# BMW_E34T_Rear_Lights.net
KiCad netlist of a schematic drawn in Altium Designer
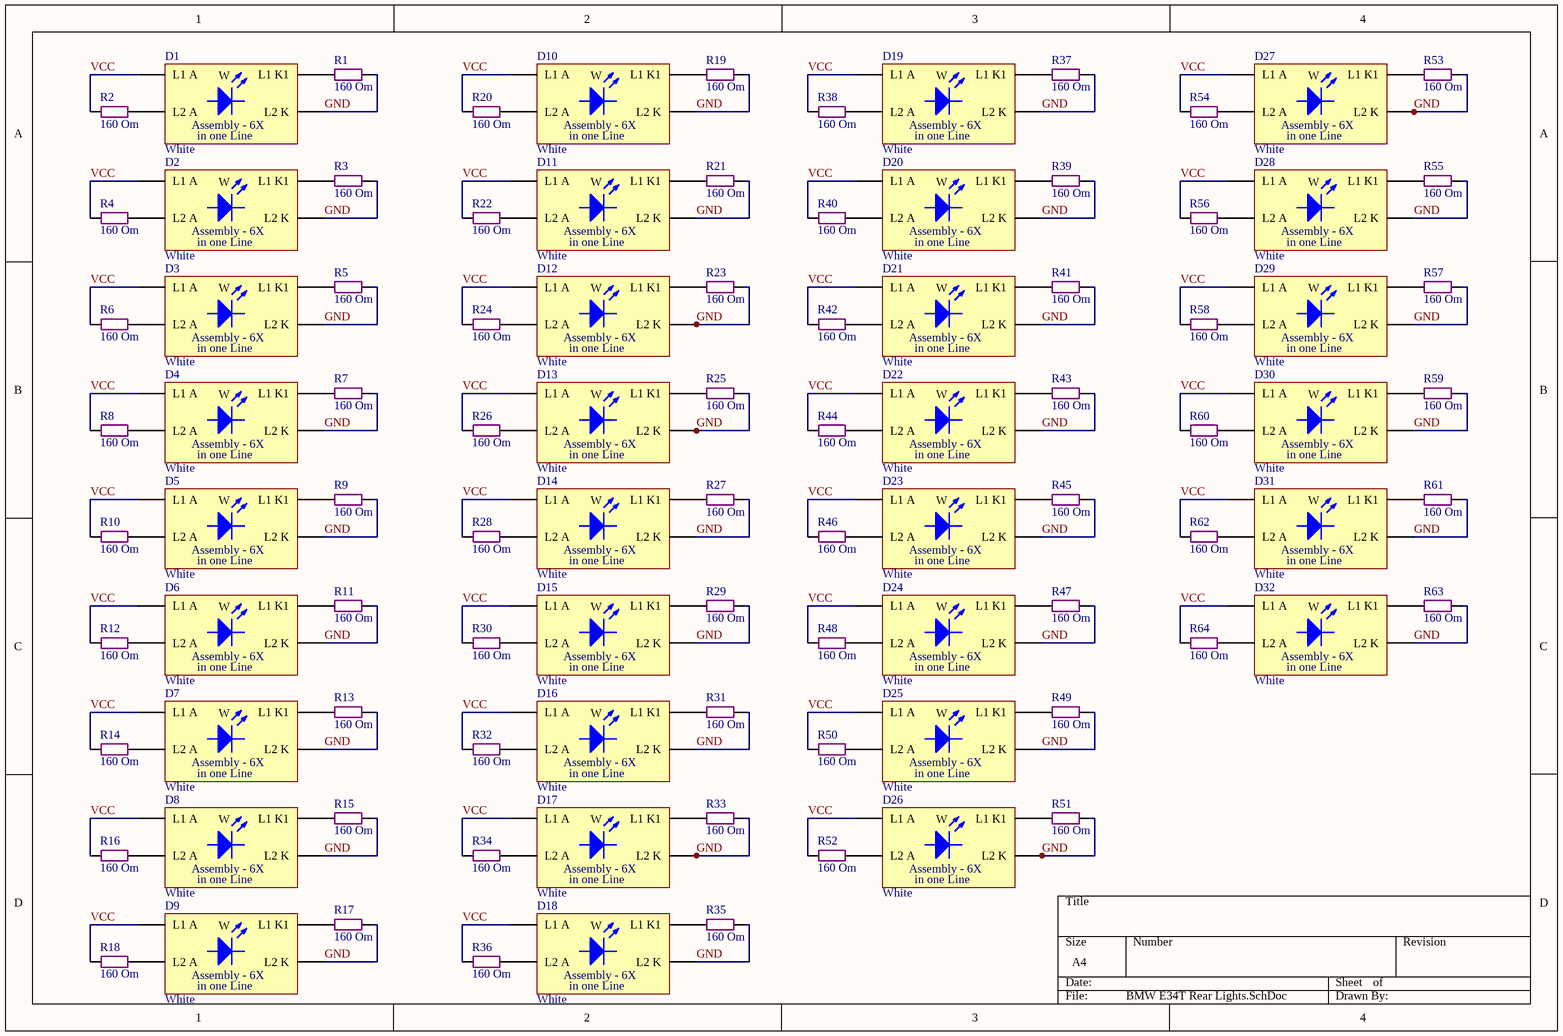
[diagram p0: BMW E34T Rear Lights.SchDoc]

(export (version "E")
  (design (tool "Eeschema 10.0.6"))
  (components
    (comp (ref "D1")
      (value "White")
      (footprint "LED:LED Assembly Round 5mm White 6X 0.5mm")
      (description "3.2-3.4v 25mA, 16-20cd")
      (libsource (lib "LED") (part "Led Assembly Round 5mm White 6X"))
    )
    (comp (ref "D2")
      (value "White")
      (footprint "LED:LED Assembly Round 5mm White 6X 0.5mm")
      (description "3.2-3.4v 25mA, 16-20cd")
      (libsource (lib "LED") (part "Led Assembly Round 5mm White 6X"))
    )
    (comp (ref "D3")
      (value "White")
      (footprint "LED:LED Assembly Round 5mm White 6X 0.5mm")
      (description "3.2-3.4v 25mA, 16-20cd")
      (libsource (lib "LED") (part "Led Assembly Round 5mm White 6X"))
    )
    (comp (ref "D4")
      (value "White")
      (footprint "LED:LED Assembly Round 5mm White 6X 0.5mm")
      (description "3.2-3.4v 25mA, 16-20cd")
      (libsource (lib "LED") (part "Led Assembly Round 5mm White 6X"))
    )
    (comp (ref "D5")
      (value "White")
      (footprint "LED:LED Assembly Round 5mm White 6X 0.5mm")
      (description "3.2-3.4v 25mA, 16-20cd")
      (libsource (lib "LED") (part "Led Assembly Round 5mm White 6X"))
    )
    (comp (ref "D6")
      (value "White")
      (footprint "LED:LED Assembly Round 5mm White 6X 0.5mm")
      (description "3.2-3.4v 25mA, 16-20cd")
      (libsource (lib "LED") (part "Led Assembly Round 5mm White 6X"))
    )
    (comp (ref "D7")
      (value "White")
      (footprint "LED:LED Assembly Round 5mm White 6X 0.5mm")
      (description "3.2-3.4v 25mA, 16-20cd")
      (libsource (lib "LED") (part "Led Assembly Round 5mm White 6X"))
    )
    (comp (ref "D8")
      (value "White")
      (footprint "LED:LED Assembly Round 5mm White 6X 0.5mm")
      (description "3.2-3.4v 25mA, 16-20cd")
      (libsource (lib "LED") (part "Led Assembly Round 5mm White 6X"))
    )
    (comp (ref "D9")
      (value "White")
      (footprint "LED:LED Assembly Round 5mm White 6X 0.5mm")
      (description "3.2-3.4v 25mA, 16-20cd")
      (libsource (lib "LED") (part "Led Assembly Round 5mm White 6X"))
    )
    (comp (ref "D10")
      (value "White")
      (footprint "LED:LED Assembly Round 5mm White 6X 0.5mm")
      (description "3.2-3.4v 25mA, 16-20cd")
      (libsource (lib "LED") (part "Led Assembly Round 5mm White 6X"))
    )
    (comp (ref "D11")
      (value "White")
      (footprint "LED:LED Assembly Round 5mm White 6X 0.5mm")
      (description "3.2-3.4v 25mA, 16-20cd")
      (libsource (lib "LED") (part "Led Assembly Round 5mm White 6X"))
    )
    (comp (ref "D12")
      (value "White")
      (footprint "LED:LED Assembly Round 5mm White 6X 0.5mm")
      (description "3.2-3.4v 25mA, 16-20cd")
      (libsource (lib "LED") (part "Led Assembly Round 5mm White 6X"))
    )
    (comp (ref "D13")
      (value "White")
      (footprint "LED:LED Assembly Round 5mm White 6X 0.5mm")
      (description "3.2-3.4v 25mA, 16-20cd")
      (libsource (lib "LED") (part "Led Assembly Round 5mm White 6X"))
    )
    (comp (ref "D14")
      (value "White")
      (footprint "LED:LED Assembly Round 5mm White 6X 0.5mm")
      (description "3.2-3.4v 25mA, 16-20cd")
      (libsource (lib "LED") (part "Led Assembly Round 5mm White 6X"))
    )
    (comp (ref "D15")
      (value "White")
      (footprint "LED:LED Assembly Round 5mm White 6X 0.5mm")
      (description "3.2-3.4v 25mA, 16-20cd")
      (libsource (lib "LED") (part "Led Assembly Round 5mm White 6X"))
    )
    (comp (ref "D16")
      (value "White")
      (footprint "LED:LED Assembly Round 5mm White 6X 0.5mm")
      (description "3.2-3.4v 25mA, 16-20cd")
      (libsource (lib "LED") (part "Led Assembly Round 5mm White 6X"))
    )
    (comp (ref "D17")
      (value "White")
      (footprint "LED:LED Assembly Round 5mm White 6X 0.5mm")
      (description "3.2-3.4v 25mA, 16-20cd")
      (libsource (lib "LED") (part "Led Assembly Round 5mm White 6X"))
    )
    (comp (ref "D18")
      (value "White")
      (footprint "LED:LED Assembly Round 5mm White 6X 0.5mm")
      (description "3.2-3.4v 25mA, 16-20cd")
      (libsource (lib "LED") (part "Led Assembly Round 5mm White 6X"))
    )
    (comp (ref "D19")
      (value "White")
      (footprint "LED:LED Assembly Round 5mm White 6X 0.5mm")
      (description "3.2-3.4v 25mA, 16-20cd")
      (libsource (lib "LED") (part "Led Assembly Round 5mm White 6X"))
    )
    (comp (ref "D20")
      (value "White")
      (footprint "LED:LED Assembly Round 5mm White 6X 0.5mm")
      (description "3.2-3.4v 25mA, 16-20cd")
      (libsource (lib "LED") (part "Led Assembly Round 5mm White 6X"))
    )
    (comp (ref "D21")
      (value "White")
      (footprint "LED:LED Assembly Round 5mm White 6X 0.5mm")
      (description "3.2-3.4v 25mA, 16-20cd")
      (libsource (lib "LED") (part "Led Assembly Round 5mm White 6X"))
    )
    (comp (ref "D22")
      (value "White")
      (footprint "LED:LED Assembly Round 5mm White 6X 0.5mm")
      (description "3.2-3.4v 25mA, 16-20cd")
      (libsource (lib "LED") (part "Led Assembly Round 5mm White 6X"))
    )
    (comp (ref "D23")
      (value "White")
      (footprint "LED:LED Assembly Round 5mm White 6X 0.5mm")
      (description "3.2-3.4v 25mA, 16-20cd")
      (libsource (lib "LED") (part "Led Assembly Round 5mm White 6X"))
    )
    (comp (ref "D24")
      (value "White")
      (footprint "LED:LED Assembly Round 5mm White 6X 0.5mm")
      (description "3.2-3.4v 25mA, 16-20cd")
      (libsource (lib "LED") (part "Led Assembly Round 5mm White 6X"))
    )
    (comp (ref "D25")
      (value "White")
      (footprint "LED:LED Assembly Round 5mm White 6X 0.5mm")
      (description "3.2-3.4v 25mA, 16-20cd")
      (libsource (lib "LED") (part "Led Assembly Round 5mm White 6X"))
    )
    (comp (ref "D26")
      (value "White")
      (footprint "LED:LED Assembly Round 5mm White 6X 0.5mm")
      (description "3.2-3.4v 25mA, 16-20cd")
      (libsource (lib "LED") (part "Led Assembly Round 5mm White 6X"))
    )
    (comp (ref "D27")
      (value "White")
      (footprint "LED:LED Assembly Round 5mm White 6X 0.5mm")
      (description "3.2-3.4v 25mA, 16-20cd")
      (libsource (lib "LED") (part "Led Assembly Round 5mm White 6X"))
    )
    (comp (ref "D28")
      (value "White")
      (footprint "LED:LED Assembly Round 5mm White 6X 0.5mm")
      (description "3.2-3.4v 25mA, 16-20cd")
      (libsource (lib "LED") (part "Led Assembly Round 5mm White 6X"))
    )
    (comp (ref "D29")
      (value "White")
      (footprint "LED:LED Assembly Round 5mm White 6X 0.5mm")
      (description "3.2-3.4v 25mA, 16-20cd")
      (libsource (lib "LED") (part "Led Assembly Round 5mm White 6X"))
    )
    (comp (ref "D30")
      (value "White")
      (footprint "LED:LED Assembly Round 5mm White 6X 0.5mm")
      (description "3.2-3.4v 25mA, 16-20cd")
      (libsource (lib "LED") (part "Led Assembly Round 5mm White 6X"))
    )
    (comp (ref "D31")
      (value "White")
      (footprint "LED:LED Assembly Round 5mm White 6X 0.5mm")
      (description "3.2-3.4v 25mA, 16-20cd")
      (libsource (lib "LED") (part "Led Assembly Round 5mm White 6X"))
    )
    (comp (ref "D32")
      (value "White")
      (footprint "LED:LED Assembly Round 5mm White 6X 0.5mm")
      (description "3.2-3.4v 25mA, 16-20cd")
      (libsource (lib "LED") (part "Led Assembly Round 5mm White 6X"))
    )
    (comp (ref "R1")
      (value "160 Om")
      (footprint "SMD 0805 (2012)")
      (libsource (lib "PassiveComponents") (part "Res SMD 0805"))
    )
    (comp (ref "R2")
      (value "160 Om")
      (footprint "SMD 0805 (2012)")
      (libsource (lib "PassiveComponents") (part "Res SMD 0805"))
    )
    (comp (ref "R3")
      (value "160 Om")
      (footprint "SMD 0805 (2012)")
      (libsource (lib "PassiveComponents") (part "Res SMD 0805"))
    )
    (comp (ref "R4")
      (value "160 Om")
      (footprint "SMD 0805 (2012)")
      (libsource (lib "PassiveComponents") (part "Res SMD 0805"))
    )
    (comp (ref "R5")
      (value "160 Om")
      (footprint "SMD 0805 (2012)")
      (libsource (lib "PassiveComponents") (part "Res SMD 0805"))
    )
    (comp (ref "R6")
      (value "160 Om")
      (footprint "SMD 0805 (2012)")
      (libsource (lib "PassiveComponents") (part "Res SMD 0805"))
    )
    (comp (ref "R7")
      (value "160 Om")
      (footprint "SMD 0805 (2012)")
      (libsource (lib "PassiveComponents") (part "Res SMD 0805"))
    )
    (comp (ref "R8")
      (value "160 Om")
      (footprint "SMD 0805 (2012)")
      (libsource (lib "PassiveComponents") (part "Res SMD 0805"))
    )
    (comp (ref "R9")
      (value "160 Om")
      (footprint "SMD 0805 (2012)")
      (libsource (lib "PassiveComponents") (part "Res SMD 0805"))
    )
    (comp (ref "R10")
      (value "160 Om")
      (footprint "SMD 0805 (2012)")
      (libsource (lib "PassiveComponents") (part "Res SMD 0805"))
    )
    (comp (ref "R11")
      (value "160 Om")
      (footprint "SMD 0805 (2012)")
      (libsource (lib "PassiveComponents") (part "Res SMD 0805"))
    )
    (comp (ref "R12")
      (value "160 Om")
      (footprint "SMD 0805 (2012)")
      (libsource (lib "PassiveComponents") (part "Res SMD 0805"))
    )
    (comp (ref "R13")
      (value "160 Om")
      (footprint "SMD 0805 (2012)")
      (libsource (lib "PassiveComponents") (part "Res SMD 0805"))
    )
    (comp (ref "R14")
      (value "160 Om")
      (footprint "SMD 0805 (2012)")
      (libsource (lib "PassiveComponents") (part "Res SMD 0805"))
    )
    (comp (ref "R15")
      (value "160 Om")
      (footprint "SMD 0805 (2012)")
      (libsource (lib "PassiveComponents") (part "Res SMD 0805"))
    )
    (comp (ref "R16")
      (value "160 Om")
      (footprint "SMD 0805 (2012)")
      (libsource (lib "PassiveComponents") (part "Res SMD 0805"))
    )
    (comp (ref "R17")
      (value "160 Om")
      (footprint "SMD 0805 (2012)")
      (libsource (lib "PassiveComponents") (part "Res SMD 0805"))
    )
    (comp (ref "R18")
      (value "160 Om")
      (footprint "SMD 0805 (2012)")
      (libsource (lib "PassiveComponents") (part "Res SMD 0805"))
    )
    (comp (ref "R19")
      (value "160 Om")
      (footprint "SMD 0805 (2012)")
      (libsource (lib "PassiveComponents") (part "Res SMD 0805"))
    )
    (comp (ref "R20")
      (value "160 Om")
      (footprint "SMD 0805 (2012)")
      (libsource (lib "PassiveComponents") (part "Res SMD 0805"))
    )
    (comp (ref "R21")
      (value "160 Om")
      (footprint "SMD 0805 (2012)")
      (libsource (lib "PassiveComponents") (part "Res SMD 0805"))
    )
    (comp (ref "R22")
      (value "160 Om")
      (footprint "SMD 0805 (2012)")
      (libsource (lib "PassiveComponents") (part "Res SMD 0805"))
    )
    (comp (ref "R23")
      (value "160 Om")
      (footprint "SMD 0805 (2012)")
      (libsource (lib "PassiveComponents") (part "Res SMD 0805"))
    )
    (comp (ref "R24")
      (value "160 Om")
      (footprint "SMD 0805 (2012)")
      (libsource (lib "PassiveComponents") (part "Res SMD 0805"))
    )
    (comp (ref "R25")
      (value "160 Om")
      (footprint "SMD 0805 (2012)")
      (libsource (lib "PassiveComponents") (part "Res SMD 0805"))
    )
    (comp (ref "R26")
      (value "160 Om")
      (footprint "SMD 0805 (2012)")
      (libsource (lib "PassiveComponents") (part "Res SMD 0805"))
    )
    (comp (ref "R27")
      (value "160 Om")
      (footprint "SMD 0805 (2012)")
      (libsource (lib "PassiveComponents") (part "Res SMD 0805"))
    )
    (comp (ref "R28")
      (value "160 Om")
      (footprint "SMD 0805 (2012)")
      (libsource (lib "PassiveComponents") (part "Res SMD 0805"))
    )
    (comp (ref "R29")
      (value "160 Om")
      (footprint "SMD 0805 (2012)")
      (libsource (lib "PassiveComponents") (part "Res SMD 0805"))
    )
    (comp (ref "R30")
      (value "160 Om")
      (footprint "SMD 0805 (2012)")
      (libsource (lib "PassiveComponents") (part "Res SMD 0805"))
    )
    (comp (ref "R31")
      (value "160 Om")
      (footprint "SMD 0805 (2012)")
      (libsource (lib "PassiveComponents") (part "Res SMD 0805"))
    )
    (comp (ref "R32")
      (value "160 Om")
      (footprint "SMD 0805 (2012)")
      (libsource (lib "PassiveComponents") (part "Res SMD 0805"))
    )
    (comp (ref "R33")
      (value "160 Om")
      (footprint "SMD 0805 (2012)")
      (libsource (lib "PassiveComponents") (part "Res SMD 0805"))
    )
    (comp (ref "R34")
      (value "160 Om")
      (footprint "SMD 0805 (2012)")
      (libsource (lib "PassiveComponents") (part "Res SMD 0805"))
    )
    (comp (ref "R35")
      (value "160 Om")
      (footprint "SMD 0805 (2012)")
      (libsource (lib "PassiveComponents") (part "Res SMD 0805"))
    )
    (comp (ref "R36")
      (value "160 Om")
      (footprint "SMD 0805 (2012)")
      (libsource (lib "PassiveComponents") (part "Res SMD 0805"))
    )
    (comp (ref "R37")
      (value "160 Om")
      (footprint "SMD 0805 (2012)")
      (libsource (lib "PassiveComponents") (part "Res SMD 0805"))
    )
    (comp (ref "R38")
      (value "160 Om")
      (footprint "SMD 0805 (2012)")
      (libsource (lib "PassiveComponents") (part "Res SMD 0805"))
    )
    (comp (ref "R39")
      (value "160 Om")
      (footprint "SMD 0805 (2012)")
      (libsource (lib "PassiveComponents") (part "Res SMD 0805"))
    )
    (comp (ref "R40")
      (value "160 Om")
      (footprint "SMD 0805 (2012)")
      (libsource (lib "PassiveComponents") (part "Res SMD 0805"))
    )
    (comp (ref "R41")
      (value "160 Om")
      (footprint "SMD 0805 (2012)")
      (libsource (lib "PassiveComponents") (part "Res SMD 0805"))
    )
    (comp (ref "R42")
      (value "160 Om")
      (footprint "SMD 0805 (2012)")
      (libsource (lib "PassiveComponents") (part "Res SMD 0805"))
    )
    (comp (ref "R43")
      (value "160 Om")
      (footprint "SMD 0805 (2012)")
      (libsource (lib "PassiveComponents") (part "Res SMD 0805"))
    )
    (comp (ref "R44")
      (value "160 Om")
      (footprint "SMD 0805 (2012)")
      (libsource (lib "PassiveComponents") (part "Res SMD 0805"))
    )
    (comp (ref "R45")
      (value "160 Om")
      (footprint "SMD 0805 (2012)")
      (libsource (lib "PassiveComponents") (part "Res SMD 0805"))
    )
    (comp (ref "R46")
      (value "160 Om")
      (footprint "SMD 0805 (2012)")
      (libsource (lib "PassiveComponents") (part "Res SMD 0805"))
    )
    (comp (ref "R47")
      (value "160 Om")
      (footprint "SMD 0805 (2012)")
      (libsource (lib "PassiveComponents") (part "Res SMD 0805"))
    )
    (comp (ref "R48")
      (value "160 Om")
      (footprint "SMD 0805 (2012)")
      (libsource (lib "PassiveComponents") (part "Res SMD 0805"))
    )
    (comp (ref "R49")
      (value "160 Om")
      (footprint "SMD 0805 (2012)")
      (libsource (lib "PassiveComponents") (part "Res SMD 0805"))
    )
    (comp (ref "R50")
      (value "160 Om")
      (footprint "SMD 0805 (2012)")
      (libsource (lib "PassiveComponents") (part "Res SMD 0805"))
    )
    (comp (ref "R51")
      (value "160 Om")
      (footprint "SMD 0805 (2012)")
      (libsource (lib "PassiveComponents") (part "Res SMD 0805"))
    )
    (comp (ref "R52")
      (value "160 Om")
      (footprint "SMD 0805 (2012)")
      (libsource (lib "PassiveComponents") (part "Res SMD 0805"))
    )
    (comp (ref "R53")
      (value "160 Om")
      (footprint "SMD 0805 (2012)")
      (libsource (lib "PassiveComponents") (part "Res SMD 0805"))
    )
    (comp (ref "R54")
      (value "160 Om")
      (footprint "SMD 0805 (2012)")
      (libsource (lib "PassiveComponents") (part "Res SMD 0805"))
    )
    (comp (ref "R55")
      (value "160 Om")
      (footprint "SMD 0805 (2012)")
      (libsource (lib "PassiveComponents") (part "Res SMD 0805"))
    )
    (comp (ref "R56")
      (value "160 Om")
      (footprint "SMD 0805 (2012)")
      (libsource (lib "PassiveComponents") (part "Res SMD 0805"))
    )
    (comp (ref "R57")
      (value "160 Om")
      (footprint "SMD 0805 (2012)")
      (libsource (lib "PassiveComponents") (part "Res SMD 0805"))
    )
    (comp (ref "R58")
      (value "160 Om")
      (footprint "SMD 0805 (2012)")
      (libsource (lib "PassiveComponents") (part "Res SMD 0805"))
    )
    (comp (ref "R59")
      (value "160 Om")
      (footprint "SMD 0805 (2012)")
      (libsource (lib "PassiveComponents") (part "Res SMD 0805"))
    )
    (comp (ref "R60")
      (value "160 Om")
      (footprint "SMD 0805 (2012)")
      (libsource (lib "PassiveComponents") (part "Res SMD 0805"))
    )
    (comp (ref "R61")
      (value "160 Om")
      (footprint "SMD 0805 (2012)")
      (libsource (lib "PassiveComponents") (part "Res SMD 0805"))
    )
    (comp (ref "R62")
      (value "160 Om")
      (footprint "SMD 0805 (2012)")
      (libsource (lib "PassiveComponents") (part "Res SMD 0805"))
    )
    (comp (ref "R63")
      (value "160 Om")
      (footprint "SMD 0805 (2012)")
      (libsource (lib "PassiveComponents") (part "Res SMD 0805"))
    )
    (comp (ref "R64")
      (value "160 Om")
      (footprint "SMD 0805 (2012)")
      (libsource (lib "PassiveComponents") (part "Res SMD 0805"))
    )
  )
  (nets
    (net (code "1") (name "/GND") (class "Default")
      (node (ref "D1") (pin "K2") (pinfunction "L2_K_K2") (pintype "passive"))
      (node (ref "D10") (pin "K2") (pinfunction "L2_K_K2") (pintype "passive"))
      (node (ref "D11") (pin "K2") (pinfunction "L2_K_K2") (pintype "passive"))
      (node (ref "D12") (pin "K2") (pinfunction "L2_K_K2") (pintype "passive"))
      (node (ref "D13") (pin "K2") (pinfunction "L2_K_K2") (pintype "passive"))
      (node (ref "D14") (pin "K2") (pinfunction "L2_K_K2") (pintype "passive"))
      (node (ref "D15") (pin "K2") (pinfunction "L2_K_K2") (pintype "passive"))
      (node (ref "D16") (pin "K2") (pinfunction "L2_K_K2") (pintype "passive"))
      (node (ref "D17") (pin "K2") (pinfunction "L2_K_K2") (pintype "passive"))
      (node (ref "D18") (pin "K2") (pinfunction "L2_K_K2") (pintype "passive"))
      (node (ref "D19") (pin "K2") (pinfunction "L2_K_K2") (pintype "passive"))
      (node (ref "D2") (pin "K2") (pinfunction "L2_K_K2") (pintype "passive"))
      (node (ref "D20") (pin "K2") (pinfunction "L2_K_K2") (pintype "passive"))
      (node (ref "D21") (pin "K2") (pinfunction "L2_K_K2") (pintype "passive"))
      (node (ref "D22") (pin "K2") (pinfunction "L2_K_K2") (pintype "passive"))
      (node (ref "D23") (pin "K2") (pinfunction "L2_K_K2") (pintype "passive"))
      (node (ref "D24") (pin "K2") (pinfunction "L2_K_K2") (pintype "passive"))
      (node (ref "D25") (pin "K2") (pinfunction "L2_K_K2") (pintype "passive"))
      (node (ref "D26") (pin "K2") (pinfunction "L2_K_K2") (pintype "passive"))
      (node (ref "D27") (pin "K2") (pinfunction "L2_K_K2") (pintype "passive"))
      (node (ref "D28") (pin "K2") (pinfunction "L2_K_K2") (pintype "passive"))
      (node (ref "D29") (pin "K2") (pinfunction "L2_K_K2") (pintype "passive"))
      (node (ref "D3") (pin "K2") (pinfunction "L2_K_K2") (pintype "passive"))
      (node (ref "D30") (pin "K2") (pinfunction "L2_K_K2") (pintype "passive"))
      (node (ref "D31") (pin "K2") (pinfunction "L2_K_K2") (pintype "passive"))
      (node (ref "D32") (pin "K2") (pinfunction "L2_K_K2") (pintype "passive"))
      (node (ref "D4") (pin "K2") (pinfunction "L2_K_K2") (pintype "passive"))
      (node (ref "D5") (pin "K2") (pinfunction "L2_K_K2") (pintype "passive"))
      (node (ref "D6") (pin "K2") (pinfunction "L2_K_K2") (pintype "passive"))
      (node (ref "D7") (pin "K2") (pinfunction "L2_K_K2") (pintype "passive"))
      (node (ref "D8") (pin "K2") (pinfunction "L2_K_K2") (pintype "passive"))
      (node (ref "D9") (pin "K2") (pinfunction "L2_K_K2") (pintype "passive"))
      (node (ref "R1") (pin "2") (pinfunction "2_2") (pintype "passive"))
      (node (ref "R11") (pin "2") (pinfunction "2_2") (pintype "passive"))
      (node (ref "R13") (pin "2") (pinfunction "2_2") (pintype "passive"))
      (node (ref "R15") (pin "2") (pinfunction "2_2") (pintype "passive"))
      (node (ref "R17") (pin "2") (pinfunction "2_2") (pintype "passive"))
      (node (ref "R19") (pin "2") (pinfunction "2_2") (pintype "passive"))
      (node (ref "R21") (pin "2") (pinfunction "2_2") (pintype "passive"))
      (node (ref "R23") (pin "2") (pinfunction "2_2") (pintype "passive"))
      (node (ref "R25") (pin "2") (pinfunction "2_2") (pintype "passive"))
      (node (ref "R27") (pin "2") (pinfunction "2_2") (pintype "passive"))
      (node (ref "R29") (pin "2") (pinfunction "2_2") (pintype "passive"))
      (node (ref "R3") (pin "2") (pinfunction "2_2") (pintype "passive"))
      (node (ref "R31") (pin "2") (pinfunction "2_2") (pintype "passive"))
      (node (ref "R33") (pin "2") (pinfunction "2_2") (pintype "passive"))
      (node (ref "R35") (pin "2") (pinfunction "2_2") (pintype "passive"))
      (node (ref "R37") (pin "2") (pinfunction "2_2") (pintype "passive"))
      (node (ref "R39") (pin "2") (pinfunction "2_2") (pintype "passive"))
      (node (ref "R41") (pin "2") (pinfunction "2_2") (pintype "passive"))
      (node (ref "R43") (pin "2") (pinfunction "2_2") (pintype "passive"))
      (node (ref "R45") (pin "2") (pinfunction "2_2") (pintype "passive"))
      (node (ref "R47") (pin "2") (pinfunction "2_2") (pintype "passive"))
      (node (ref "R49") (pin "2") (pinfunction "2_2") (pintype "passive"))
      (node (ref "R5") (pin "2") (pinfunction "2_2") (pintype "passive"))
      (node (ref "R51") (pin "2") (pinfunction "2_2") (pintype "passive"))
      (node (ref "R53") (pin "2") (pinfunction "2_2") (pintype "passive"))
      (node (ref "R55") (pin "2") (pinfunction "2_2") (pintype "passive"))
      (node (ref "R57") (pin "2") (pinfunction "2_2") (pintype "passive"))
      (node (ref "R59") (pin "2") (pinfunction "2_2") (pintype "passive"))
      (node (ref "R61") (pin "2") (pinfunction "2_2") (pintype "passive"))
      (node (ref "R63") (pin "2") (pinfunction "2_2") (pintype "passive"))
      (node (ref "R7") (pin "2") (pinfunction "2_2") (pintype "passive"))
      (node (ref "R9") (pin "2") (pinfunction "2_2") (pintype "passive"))
    )
    (net (code "2") (name "/VCC") (class "Default")
      (node (ref "D1") (pin "A1") (pinfunction "L1_A_A1") (pintype "passive"))
      (node (ref "D10") (pin "A1") (pinfunction "L1_A_A1") (pintype "passive"))
      (node (ref "D11") (pin "A1") (pinfunction "L1_A_A1") (pintype "passive"))
      (node (ref "D12") (pin "A1") (pinfunction "L1_A_A1") (pintype "passive"))
      (node (ref "D13") (pin "A1") (pinfunction "L1_A_A1") (pintype "passive"))
      (node (ref "D14") (pin "A1") (pinfunction "L1_A_A1") (pintype "passive"))
      (node (ref "D15") (pin "A1") (pinfunction "L1_A_A1") (pintype "passive"))
      (node (ref "D16") (pin "A1") (pinfunction "L1_A_A1") (pintype "passive"))
      (node (ref "D17") (pin "A1") (pinfunction "L1_A_A1") (pintype "passive"))
      (node (ref "D18") (pin "A1") (pinfunction "L1_A_A1") (pintype "passive"))
      (node (ref "D19") (pin "A1") (pinfunction "L1_A_A1") (pintype "passive"))
      (node (ref "D2") (pin "A1") (pinfunction "L1_A_A1") (pintype "passive"))
      (node (ref "D20") (pin "A1") (pinfunction "L1_A_A1") (pintype "passive"))
      (node (ref "D21") (pin "A1") (pinfunction "L1_A_A1") (pintype "passive"))
      (node (ref "D22") (pin "A1") (pinfunction "L1_A_A1") (pintype "passive"))
      (node (ref "D23") (pin "A1") (pinfunction "L1_A_A1") (pintype "passive"))
      (node (ref "D24") (pin "A1") (pinfunction "L1_A_A1") (pintype "passive"))
      (node (ref "D25") (pin "A1") (pinfunction "L1_A_A1") (pintype "passive"))
      (node (ref "D26") (pin "A1") (pinfunction "L1_A_A1") (pintype "passive"))
      (node (ref "D27") (pin "A1") (pinfunction "L1_A_A1") (pintype "passive"))
      (node (ref "D28") (pin "A1") (pinfunction "L1_A_A1") (pintype "passive"))
      (node (ref "D29") (pin "A1") (pinfunction "L1_A_A1") (pintype "passive"))
      (node (ref "D3") (pin "A1") (pinfunction "L1_A_A1") (pintype "passive"))
      (node (ref "D30") (pin "A1") (pinfunction "L1_A_A1") (pintype "passive"))
      (node (ref "D31") (pin "A1") (pinfunction "L1_A_A1") (pintype "passive"))
      (node (ref "D32") (pin "A1") (pinfunction "L1_A_A1") (pintype "passive"))
      (node (ref "D4") (pin "A1") (pinfunction "L1_A_A1") (pintype "passive"))
      (node (ref "D5") (pin "A1") (pinfunction "L1_A_A1") (pintype "passive"))
      (node (ref "D6") (pin "A1") (pinfunction "L1_A_A1") (pintype "passive"))
      (node (ref "D7") (pin "A1") (pinfunction "L1_A_A1") (pintype "passive"))
      (node (ref "D8") (pin "A1") (pinfunction "L1_A_A1") (pintype "passive"))
      (node (ref "D9") (pin "A1") (pinfunction "L1_A_A1") (pintype "passive"))
      (node (ref "R10") (pin "1") (pinfunction "1_1") (pintype "passive"))
      (node (ref "R12") (pin "1") (pinfunction "1_1") (pintype "passive"))
      (node (ref "R14") (pin "1") (pinfunction "1_1") (pintype "passive"))
      (node (ref "R16") (pin "1") (pinfunction "1_1") (pintype "passive"))
      (node (ref "R18") (pin "1") (pinfunction "1_1") (pintype "passive"))
      (node (ref "R2") (pin "1") (pinfunction "1_1") (pintype "passive"))
      (node (ref "R20") (pin "1") (pinfunction "1_1") (pintype "passive"))
      (node (ref "R22") (pin "1") (pinfunction "1_1") (pintype "passive"))
      (node (ref "R24") (pin "1") (pinfunction "1_1") (pintype "passive"))
      (node (ref "R26") (pin "1") (pinfunction "1_1") (pintype "passive"))
      (node (ref "R28") (pin "1") (pinfunction "1_1") (pintype "passive"))
      (node (ref "R30") (pin "1") (pinfunction "1_1") (pintype "passive"))
      (node (ref "R32") (pin "1") (pinfunction "1_1") (pintype "passive"))
      (node (ref "R34") (pin "1") (pinfunction "1_1") (pintype "passive"))
      (node (ref "R36") (pin "1") (pinfunction "1_1") (pintype "passive"))
      (node (ref "R38") (pin "1") (pinfunction "1_1") (pintype "passive"))
      (node (ref "R4") (pin "1") (pinfunction "1_1") (pintype "passive"))
      (node (ref "R40") (pin "1") (pinfunction "1_1") (pintype "passive"))
      (node (ref "R42") (pin "1") (pinfunction "1_1") (pintype "passive"))
      (node (ref "R44") (pin "1") (pinfunction "1_1") (pintype "passive"))
      (node (ref "R46") (pin "1") (pinfunction "1_1") (pintype "passive"))
      (node (ref "R48") (pin "1") (pinfunction "1_1") (pintype "passive"))
      (node (ref "R50") (pin "1") (pinfunction "1_1") (pintype "passive"))
      (node (ref "R52") (pin "1") (pinfunction "1_1") (pintype "passive"))
      (node (ref "R54") (pin "1") (pinfunction "1_1") (pintype "passive"))
      (node (ref "R56") (pin "1") (pinfunction "1_1") (pintype "passive"))
      (node (ref "R58") (pin "1") (pinfunction "1_1") (pintype "passive"))
      (node (ref "R6") (pin "1") (pinfunction "1_1") (pintype "passive"))
      (node (ref "R60") (pin "1") (pinfunction "1_1") (pintype "passive"))
      (node (ref "R62") (pin "1") (pinfunction "1_1") (pintype "passive"))
      (node (ref "R64") (pin "1") (pinfunction "1_1") (pintype "passive"))
      (node (ref "R8") (pin "1") (pinfunction "1_1") (pintype "passive"))
    )
    (net (code "3") (name "Net-(D1-L1_K1)") (class "Default")
      (node (ref "D1") (pin "K1") (pinfunction "L1_K1_K1") (pintype "passive"))
      (node (ref "R1") (pin "1") (pinfunction "1_1") (pintype "passive"))
    )
    (net (code "4") (name "Net-(D1-L2_A)") (class "Default")
      (node (ref "D1") (pin "A2") (pinfunction "L2_A_A2") (pintype "passive"))
      (node (ref "R2") (pin "2") (pinfunction "2_2") (pintype "passive"))
    )
    (net (code "5") (name "Net-(D2-L1_K1)") (class "Default")
      (node (ref "D2") (pin "K1") (pinfunction "L1_K1_K1") (pintype "passive"))
      (node (ref "R3") (pin "1") (pinfunction "1_1") (pintype "passive"))
    )
    (net (code "6") (name "Net-(D2-L2_A)") (class "Default")
      (node (ref "D2") (pin "A2") (pinfunction "L2_A_A2") (pintype "passive"))
      (node (ref "R4") (pin "2") (pinfunction "2_2") (pintype "passive"))
    )
    (net (code "7") (name "Net-(D3-L1_K1)") (class "Default")
      (node (ref "D3") (pin "K1") (pinfunction "L1_K1_K1") (pintype "passive"))
      (node (ref "R5") (pin "1") (pinfunction "1_1") (pintype "passive"))
    )
    (net (code "8") (name "Net-(D3-L2_A)") (class "Default")
      (node (ref "D3") (pin "A2") (pinfunction "L2_A_A2") (pintype "passive"))
      (node (ref "R6") (pin "2") (pinfunction "2_2") (pintype "passive"))
    )
    (net (code "9") (name "Net-(D4-L1_K1)") (class "Default")
      (node (ref "D4") (pin "K1") (pinfunction "L1_K1_K1") (pintype "passive"))
      (node (ref "R7") (pin "1") (pinfunction "1_1") (pintype "passive"))
    )
    (net (code "10") (name "Net-(D4-L2_A)") (class "Default")
      (node (ref "D4") (pin "A2") (pinfunction "L2_A_A2") (pintype "passive"))
      (node (ref "R8") (pin "2") (pinfunction "2_2") (pintype "passive"))
    )
    (net (code "11") (name "Net-(D5-L1_K1)") (class "Default")
      (node (ref "D5") (pin "K1") (pinfunction "L1_K1_K1") (pintype "passive"))
      (node (ref "R9") (pin "1") (pinfunction "1_1") (pintype "passive"))
    )
    (net (code "12") (name "Net-(D5-L2_A)") (class "Default")
      (node (ref "D5") (pin "A2") (pinfunction "L2_A_A2") (pintype "passive"))
      (node (ref "R10") (pin "2") (pinfunction "2_2") (pintype "passive"))
    )
    (net (code "13") (name "Net-(D6-L1_K1)") (class "Default")
      (node (ref "D6") (pin "K1") (pinfunction "L1_K1_K1") (pintype "passive"))
      (node (ref "R11") (pin "1") (pinfunction "1_1") (pintype "passive"))
    )
    (net (code "14") (name "Net-(D6-L2_A)") (class "Default")
      (node (ref "D6") (pin "A2") (pinfunction "L2_A_A2") (pintype "passive"))
      (node (ref "R12") (pin "2") (pinfunction "2_2") (pintype "passive"))
    )
    (net (code "15") (name "Net-(D7-L1_K1)") (class "Default")
      (node (ref "D7") (pin "K1") (pinfunction "L1_K1_K1") (pintype "passive"))
      (node (ref "R13") (pin "1") (pinfunction "1_1") (pintype "passive"))
    )
    (net (code "16") (name "Net-(D7-L2_A)") (class "Default")
      (node (ref "D7") (pin "A2") (pinfunction "L2_A_A2") (pintype "passive"))
      (node (ref "R14") (pin "2") (pinfunction "2_2") (pintype "passive"))
    )
    (net (code "17") (name "Net-(D8-L1_K1)") (class "Default")
      (node (ref "D8") (pin "K1") (pinfunction "L1_K1_K1") (pintype "passive"))
      (node (ref "R15") (pin "1") (pinfunction "1_1") (pintype "passive"))
    )
    (net (code "18") (name "Net-(D8-L2_A)") (class "Default")
      (node (ref "D8") (pin "A2") (pinfunction "L2_A_A2") (pintype "passive"))
      (node (ref "R16") (pin "2") (pinfunction "2_2") (pintype "passive"))
    )
    (net (code "19") (name "Net-(D9-L1_K1)") (class "Default")
      (node (ref "D9") (pin "K1") (pinfunction "L1_K1_K1") (pintype "passive"))
      (node (ref "R17") (pin "1") (pinfunction "1_1") (pintype "passive"))
    )
    (net (code "20") (name "Net-(D9-L2_A)") (class "Default")
      (node (ref "D9") (pin "A2") (pinfunction "L2_A_A2") (pintype "passive"))
      (node (ref "R18") (pin "2") (pinfunction "2_2") (pintype "passive"))
    )
    (net (code "21") (name "Net-(D10-L1_K1)") (class "Default")
      (node (ref "D10") (pin "K1") (pinfunction "L1_K1_K1") (pintype "passive"))
      (node (ref "R19") (pin "1") (pinfunction "1_1") (pintype "passive"))
    )
    (net (code "22") (name "Net-(D10-L2_A)") (class "Default")
      (node (ref "D10") (pin "A2") (pinfunction "L2_A_A2") (pintype "passive"))
      (node (ref "R20") (pin "2") (pinfunction "2_2") (pintype "passive"))
    )
    (net (code "23") (name "Net-(D11-L1_K1)") (class "Default")
      (node (ref "D11") (pin "K1") (pinfunction "L1_K1_K1") (pintype "passive"))
      (node (ref "R21") (pin "1") (pinfunction "1_1") (pintype "passive"))
    )
    (net (code "24") (name "Net-(D11-L2_A)") (class "Default")
      (node (ref "D11") (pin "A2") (pinfunction "L2_A_A2") (pintype "passive"))
      (node (ref "R22") (pin "2") (pinfunction "2_2") (pintype "passive"))
    )
    (net (code "25") (name "Net-(D12-L1_K1)") (class "Default")
      (node (ref "D12") (pin "K1") (pinfunction "L1_K1_K1") (pintype "passive"))
      (node (ref "R23") (pin "1") (pinfunction "1_1") (pintype "passive"))
    )
    (net (code "26") (name "Net-(D12-L2_A)") (class "Default")
      (node (ref "D12") (pin "A2") (pinfunction "L2_A_A2") (pintype "passive"))
      (node (ref "R24") (pin "2") (pinfunction "2_2") (pintype "passive"))
    )
    (net (code "27") (name "Net-(D13-L1_K1)") (class "Default")
      (node (ref "D13") (pin "K1") (pinfunction "L1_K1_K1") (pintype "passive"))
      (node (ref "R25") (pin "1") (pinfunction "1_1") (pintype "passive"))
    )
    (net (code "28") (name "Net-(D13-L2_A)") (class "Default")
      (node (ref "D13") (pin "A2") (pinfunction "L2_A_A2") (pintype "passive"))
      (node (ref "R26") (pin "2") (pinfunction "2_2") (pintype "passive"))
    )
    (net (code "29") (name "Net-(D14-L1_K1)") (class "Default")
      (node (ref "D14") (pin "K1") (pinfunction "L1_K1_K1") (pintype "passive"))
      (node (ref "R27") (pin "1") (pinfunction "1_1") (pintype "passive"))
    )
    (net (code "30") (name "Net-(D14-L2_A)") (class "Default")
      (node (ref "D14") (pin "A2") (pinfunction "L2_A_A2") (pintype "passive"))
      (node (ref "R28") (pin "2") (pinfunction "2_2") (pintype "passive"))
    )
    (net (code "31") (name "Net-(D15-L1_K1)") (class "Default")
      (node (ref "D15") (pin "K1") (pinfunction "L1_K1_K1") (pintype "passive"))
      (node (ref "R29") (pin "1") (pinfunction "1_1") (pintype "passive"))
    )
    (net (code "32") (name "Net-(D15-L2_A)") (class "Default")
      (node (ref "D15") (pin "A2") (pinfunction "L2_A_A2") (pintype "passive"))
      (node (ref "R30") (pin "2") (pinfunction "2_2") (pintype "passive"))
    )
    (net (code "33") (name "Net-(D16-L1_K1)") (class "Default")
      (node (ref "D16") (pin "K1") (pinfunction "L1_K1_K1") (pintype "passive"))
      (node (ref "R31") (pin "1") (pinfunction "1_1") (pintype "passive"))
    )
    (net (code "34") (name "Net-(D16-L2_A)") (class "Default")
      (node (ref "D16") (pin "A2") (pinfunction "L2_A_A2") (pintype "passive"))
      (node (ref "R32") (pin "2") (pinfunction "2_2") (pintype "passive"))
    )
    (net (code "35") (name "Net-(D17-L1_K1)") (class "Default")
      (node (ref "D17") (pin "K1") (pinfunction "L1_K1_K1") (pintype "passive"))
      (node (ref "R33") (pin "1") (pinfunction "1_1") (pintype "passive"))
    )
    (net (code "36") (name "Net-(D17-L2_A)") (class "Default")
      (node (ref "D17") (pin "A2") (pinfunction "L2_A_A2") (pintype "passive"))
      (node (ref "R34") (pin "2") (pinfunction "2_2") (pintype "passive"))
    )
    (net (code "37") (name "Net-(D18-L1_K1)") (class "Default")
      (node (ref "D18") (pin "K1") (pinfunction "L1_K1_K1") (pintype "passive"))
      (node (ref "R35") (pin "1") (pinfunction "1_1") (pintype "passive"))
    )
    (net (code "38") (name "Net-(D18-L2_A)") (class "Default")
      (node (ref "D18") (pin "A2") (pinfunction "L2_A_A2") (pintype "passive"))
      (node (ref "R36") (pin "2") (pinfunction "2_2") (pintype "passive"))
    )
    (net (code "39") (name "Net-(D19-L1_K1)") (class "Default")
      (node (ref "D19") (pin "K1") (pinfunction "L1_K1_K1") (pintype "passive"))
      (node (ref "R37") (pin "1") (pinfunction "1_1") (pintype "passive"))
    )
    (net (code "40") (name "Net-(D19-L2_A)") (class "Default")
      (node (ref "D19") (pin "A2") (pinfunction "L2_A_A2") (pintype "passive"))
      (node (ref "R38") (pin "2") (pinfunction "2_2") (pintype "passive"))
    )
    (net (code "41") (name "Net-(D20-L1_K1)") (class "Default")
      (node (ref "D20") (pin "K1") (pinfunction "L1_K1_K1") (pintype "passive"))
      (node (ref "R39") (pin "1") (pinfunction "1_1") (pintype "passive"))
    )
    (net (code "42") (name "Net-(D20-L2_A)") (class "Default")
      (node (ref "D20") (pin "A2") (pinfunction "L2_A_A2") (pintype "passive"))
      (node (ref "R40") (pin "2") (pinfunction "2_2") (pintype "passive"))
    )
    (net (code "43") (name "Net-(D21-L1_K1)") (class "Default")
      (node (ref "D21") (pin "K1") (pinfunction "L1_K1_K1") (pintype "passive"))
      (node (ref "R41") (pin "1") (pinfunction "1_1") (pintype "passive"))
    )
    (net (code "44") (name "Net-(D21-L2_A)") (class "Default")
      (node (ref "D21") (pin "A2") (pinfunction "L2_A_A2") (pintype "passive"))
      (node (ref "R42") (pin "2") (pinfunction "2_2") (pintype "passive"))
    )
    (net (code "45") (name "Net-(D22-L1_K1)") (class "Default")
      (node (ref "D22") (pin "K1") (pinfunction "L1_K1_K1") (pintype "passive"))
      (node (ref "R43") (pin "1") (pinfunction "1_1") (pintype "passive"))
    )
    (net (code "46") (name "Net-(D22-L2_A)") (class "Default")
      (node (ref "D22") (pin "A2") (pinfunction "L2_A_A2") (pintype "passive"))
      (node (ref "R44") (pin "2") (pinfunction "2_2") (pintype "passive"))
    )
    (net (code "47") (name "Net-(D23-L1_K1)") (class "Default")
      (node (ref "D23") (pin "K1") (pinfunction "L1_K1_K1") (pintype "passive"))
      (node (ref "R45") (pin "1") (pinfunction "1_1") (pintype "passive"))
    )
    (net (code "48") (name "Net-(D23-L2_A)") (class "Default")
      (node (ref "D23") (pin "A2") (pinfunction "L2_A_A2") (pintype "passive"))
      (node (ref "R46") (pin "2") (pinfunction "2_2") (pintype "passive"))
    )
    (net (code "49") (name "Net-(D24-L1_K1)") (class "Default")
      (node (ref "D24") (pin "K1") (pinfunction "L1_K1_K1") (pintype "passive"))
      (node (ref "R47") (pin "1") (pinfunction "1_1") (pintype "passive"))
    )
    (net (code "50") (name "Net-(D24-L2_A)") (class "Default")
      (node (ref "D24") (pin "A2") (pinfunction "L2_A_A2") (pintype "passive"))
      (node (ref "R48") (pin "2") (pinfunction "2_2") (pintype "passive"))
    )
    (net (code "51") (name "Net-(D25-L1_K1)") (class "Default")
      (node (ref "D25") (pin "K1") (pinfunction "L1_K1_K1") (pintype "passive"))
      (node (ref "R49") (pin "1") (pinfunction "1_1") (pintype "passive"))
    )
    (net (code "52") (name "Net-(D25-L2_A)") (class "Default")
      (node (ref "D25") (pin "A2") (pinfunction "L2_A_A2") (pintype "passive"))
      (node (ref "R50") (pin "2") (pinfunction "2_2") (pintype "passive"))
    )
    (net (code "53") (name "Net-(D26-L1_K1)") (class "Default")
      (node (ref "D26") (pin "K1") (pinfunction "L1_K1_K1") (pintype "passive"))
      (node (ref "R51") (pin "1") (pinfunction "1_1") (pintype "passive"))
    )
    (net (code "54") (name "Net-(D26-L2_A)") (class "Default")
      (node (ref "D26") (pin "A2") (pinfunction "L2_A_A2") (pintype "passive"))
      (node (ref "R52") (pin "2") (pinfunction "2_2") (pintype "passive"))
    )
    (net (code "55") (name "Net-(D27-L1_K1)") (class "Default")
      (node (ref "D27") (pin "K1") (pinfunction "L1_K1_K1") (pintype "passive"))
      (node (ref "R53") (pin "1") (pinfunction "1_1") (pintype "passive"))
    )
    (net (code "56") (name "Net-(D27-L2_A)") (class "Default")
      (node (ref "D27") (pin "A2") (pinfunction "L2_A_A2") (pintype "passive"))
      (node (ref "R54") (pin "2") (pinfunction "2_2") (pintype "passive"))
    )
    (net (code "57") (name "Net-(D28-L1_K1)") (class "Default")
      (node (ref "D28") (pin "K1") (pinfunction "L1_K1_K1") (pintype "passive"))
      (node (ref "R55") (pin "1") (pinfunction "1_1") (pintype "passive"))
    )
    (net (code "58") (name "Net-(D28-L2_A)") (class "Default")
      (node (ref "D28") (pin "A2") (pinfunction "L2_A_A2") (pintype "passive"))
      (node (ref "R56") (pin "2") (pinfunction "2_2") (pintype "passive"))
    )
    (net (code "59") (name "Net-(D29-L1_K1)") (class "Default")
      (node (ref "D29") (pin "K1") (pinfunction "L1_K1_K1") (pintype "passive"))
      (node (ref "R57") (pin "1") (pinfunction "1_1") (pintype "passive"))
    )
    (net (code "60") (name "Net-(D29-L2_A)") (class "Default")
      (node (ref "D29") (pin "A2") (pinfunction "L2_A_A2") (pintype "passive"))
      (node (ref "R58") (pin "2") (pinfunction "2_2") (pintype "passive"))
    )
    (net (code "61") (name "Net-(D30-L1_K1)") (class "Default")
      (node (ref "D30") (pin "K1") (pinfunction "L1_K1_K1") (pintype "passive"))
      (node (ref "R59") (pin "1") (pinfunction "1_1") (pintype "passive"))
    )
    (net (code "62") (name "Net-(D30-L2_A)") (class "Default")
      (node (ref "D30") (pin "A2") (pinfunction "L2_A_A2") (pintype "passive"))
      (node (ref "R60") (pin "2") (pinfunction "2_2") (pintype "passive"))
    )
    (net (code "63") (name "Net-(D31-L1_K1)") (class "Default")
      (node (ref "D31") (pin "K1") (pinfunction "L1_K1_K1") (pintype "passive"))
      (node (ref "R61") (pin "1") (pinfunction "1_1") (pintype "passive"))
    )
    (net (code "64") (name "Net-(D31-L2_A)") (class "Default")
      (node (ref "D31") (pin "A2") (pinfunction "L2_A_A2") (pintype "passive"))
      (node (ref "R62") (pin "2") (pinfunction "2_2") (pintype "passive"))
    )
    (net (code "65") (name "Net-(D32-L1_K1)") (class "Default")
      (node (ref "D32") (pin "K1") (pinfunction "L1_K1_K1") (pintype "passive"))
      (node (ref "R63") (pin "1") (pinfunction "1_1") (pintype "passive"))
    )
    (net (code "66") (name "Net-(D32-L2_A)") (class "Default")
      (node (ref "D32") (pin "A2") (pinfunction "L2_A_A2") (pintype "passive"))
      (node (ref "R64") (pin "2") (pinfunction "2_2") (pintype "passive"))
    )
  )
)
